# Irrigatron.net
KiCad netlist of a schematic drawn in EasyEDA
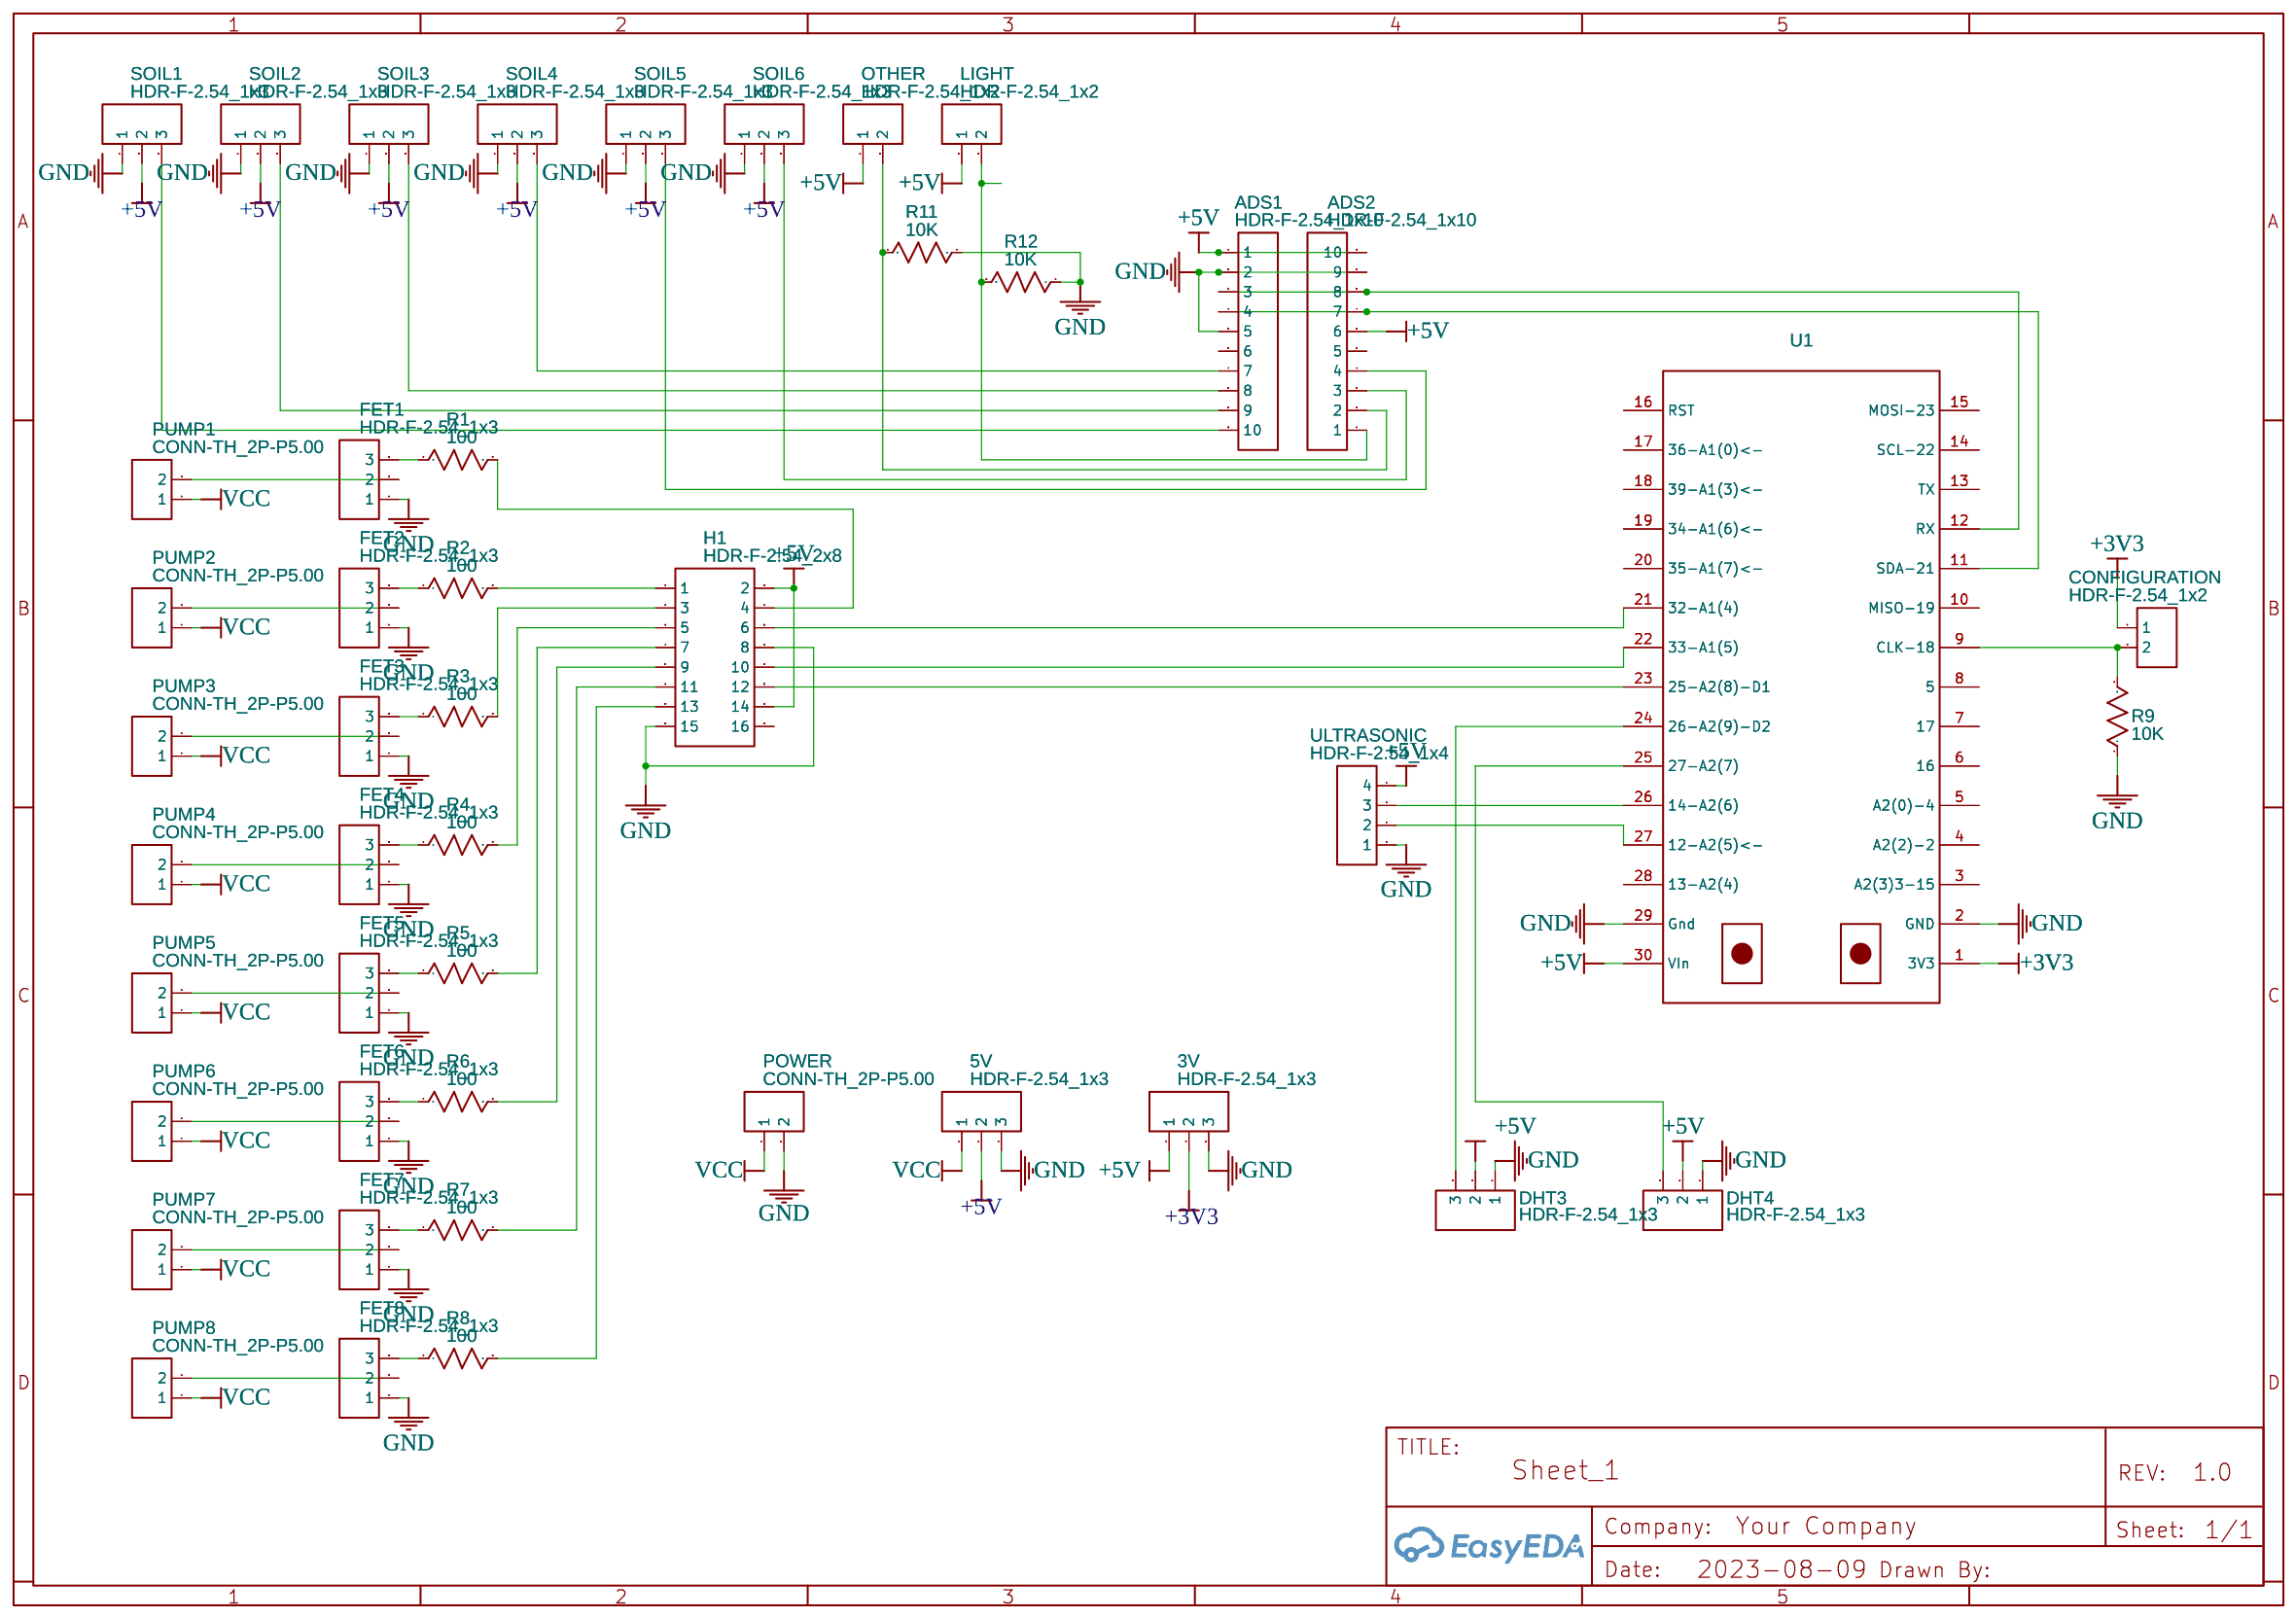
[diagram p0: schematic sheet]

(export (version "E")
  (design (tool "Eeschema 10.0.6"))
  (components
    (comp (ref "3V") (value "HDR-F-2.54_1x3") (libsource (lib "") (part "HDR-F-2.54_1x3_3")))
    (comp (ref "5V") (value "HDR-F-2.54_1x3") (libsource (lib "") (part "HDR-F-2.54_1x3")))
    (comp (ref "ADS1") (value "HDR-F-2.54_1x10") (libsource (lib "") (part "HDR-F-2.54_1x10_1")))
    (comp (ref "ADS2") (value "HDR-F-2.54_1x10") (libsource (lib "") (part "HDR-F-2.54_1x10")))
    (comp (ref "CONFIGURATION") (value "HDR-F-2.54_1x2") (libsource (lib "") (part "HDR-F-2.54_1x2_1")))
    (comp (ref "DHT3") (value "HDR-F-2.54_1x3") (libsource (lib "") (part "HDR-F-2.54_1x3_4")))
    (comp (ref "DHT4") (value "HDR-F-2.54_1x3") (libsource (lib "") (part "HDR-F-2.54_1x3_4")))
    (comp (ref "FET1") (value "HDR-F-2.54_1x3") (libsource (lib "") (part "HDR-F-2.54_1x3_1")))
    (comp (ref "FET2") (value "HDR-F-2.54_1x3") (libsource (lib "") (part "HDR-F-2.54_1x3_1")))
    (comp (ref "FET3") (value "HDR-F-2.54_1x3") (libsource (lib "") (part "HDR-F-2.54_1x3_1")))
    (comp (ref "FET4") (value "HDR-F-2.54_1x3") (libsource (lib "") (part "HDR-F-2.54_1x3_1")))
    (comp (ref "FET5") (value "HDR-F-2.54_1x3") (libsource (lib "") (part "HDR-F-2.54_1x3_1")))
    (comp (ref "FET6") (value "HDR-F-2.54_1x3") (libsource (lib "") (part "HDR-F-2.54_1x3_1")))
    (comp (ref "FET7") (value "HDR-F-2.54_1x3") (libsource (lib "") (part "HDR-F-2.54_1x3_1")))
    (comp (ref "FET8") (value "HDR-F-2.54_1x3") (libsource (lib "") (part "HDR-F-2.54_1x3_1")))
    (comp (ref "H1") (value "HDR-F-2.54_2x8") (libsource (lib "") (part "HDR-F-2.54_2x8")))
    (comp (ref "LIGHT") (value "HDR-F-2.54_1x2") (libsource (lib "") (part "HDR-F-2.54_1x2_2")))
    (comp (ref "OTHER") (value "HDR-F-2.54_1x2") (libsource (lib "") (part "HDR-F-2.54_1x2")))
    (comp (ref "POWER") (value "CONN-TH_2P-P5.00") (libsource (lib "") (part "CONN-TH_2P-P5.00_1")))
    (comp (ref "PUMP1") (value "CONN-TH_2P-P5.00") (libsource (lib "") (part "CONN-TH_2P-P5.00")))
    (comp (ref "PUMP2") (value "CONN-TH_2P-P5.00") (libsource (lib "") (part "CONN-TH_2P-P5.00")))
    (comp (ref "PUMP3") (value "CONN-TH_2P-P5.00") (libsource (lib "") (part "CONN-TH_2P-P5.00")))
    (comp (ref "PUMP4") (value "CONN-TH_2P-P5.00") (libsource (lib "") (part "CONN-TH_2P-P5.00")))
    (comp (ref "PUMP5") (value "CONN-TH_2P-P5.00") (libsource (lib "") (part "CONN-TH_2P-P5.00")))
    (comp (ref "PUMP6") (value "CONN-TH_2P-P5.00") (libsource (lib "") (part "CONN-TH_2P-P5.00")))
    (comp (ref "PUMP7") (value "CONN-TH_2P-P5.00") (libsource (lib "") (part "CONN-TH_2P-P5.00")))
    (comp (ref "PUMP8") (value "CONN-TH_2P-P5.00") (libsource (lib "") (part "CONN-TH_2P-P5.00")))
    (comp (ref "R1") (value "100") (libsource (lib "") (part "R_0603_US_1")))
    (comp (ref "R2") (value "100") (libsource (lib "") (part "R_0603_US_1")))
    (comp (ref "R3") (value "100") (libsource (lib "") (part "R_0603_US_1")))
    (comp (ref "R4") (value "100") (libsource (lib "") (part "R_0603_US_1")))
    (comp (ref "R5") (value "100") (libsource (lib "") (part "R_0603_US_1")))
    (comp (ref "R6") (value "100") (libsource (lib "") (part "R_0603_US_1")))
    (comp (ref "R7") (value "100") (libsource (lib "") (part "R_0603_US_1")))
    (comp (ref "R8") (value "100") (libsource (lib "") (part "R_0603_US_1")))
    (comp (ref "R9") (value "10K") (libsource (lib "") (part "R_0603_US_2")))
    (comp (ref "R11") (value "10K") (libsource (lib "") (part "R_0603_US")))
    (comp (ref "R12") (value "10K") (libsource (lib "") (part "R_0603_US")))
    (comp (ref "SOIL1") (value "HDR-F-2.54_1x3") (libsource (lib "") (part "HDR-F-2.54_1x3_2")))
    (comp (ref "SOIL2") (value "HDR-F-2.54_1x3") (libsource (lib "") (part "HDR-F-2.54_1x3_2")))
    (comp (ref "SOIL3") (value "HDR-F-2.54_1x3") (libsource (lib "") (part "HDR-F-2.54_1x3_2")))
    (comp (ref "SOIL4") (value "HDR-F-2.54_1x3") (libsource (lib "") (part "HDR-F-2.54_1x3_2")))
    (comp (ref "SOIL5") (value "HDR-F-2.54_1x3") (libsource (lib "") (part "HDR-F-2.54_1x3_2")))
    (comp (ref "SOIL6") (value "HDR-F-2.54_1x3") (libsource (lib "") (part "HDR-F-2.54_1x3_2")))
    (comp (ref "U1") (value "NO") (libsource (lib "") (part "DOIT ESP32 DEVKIT V1 (30pins)")))
    (comp (ref "ULTRASONIC") (value "HDR-F-2.54_1x4") (libsource (lib "") (part "HDR-F-2.54_1x4")))
  )
  (nets
    (net (code "1") (name "+3V3") (class "Default")
      (node (ref "3V") (pin "2") (pinfunction "2_2") (pintype "input"))
      (node (ref "CONFIGURATION") (pin "1") (pinfunction "1_1") (pintype "input"))
      (node (ref "U1") (pin "1") (pinfunction "3V3_1") (pintype "unspecified"))
    )
    (net (code "2") (name "+5V") (class "Default")
      (node (ref "3V") (pin "1") (pinfunction "1_1") (pintype "input"))
      (node (ref "5V") (pin "2") (pinfunction "2_2") (pintype "input"))
      (node (ref "ADS1") (pin "1") (pinfunction "1_1") (pintype "unspecified"))
      (node (ref "ADS2") (pin "10") (pinfunction "10_10") (pintype "unspecified"))
      (node (ref "ADS2") (pin "6") (pinfunction "6_6") (pintype "unspecified"))
      (node (ref "DHT3") (pin "2") (pinfunction "2_2") (pintype "input"))
      (node (ref "DHT4") (pin "2") (pinfunction "2_2") (pintype "input"))
      (node (ref "H1") (pin "14") (pinfunction "14_14") (pintype "input"))
      (node (ref "H1") (pin "2") (pinfunction "2_2") (pintype "input"))
      (node (ref "LIGHT") (pin "1") (pinfunction "1_1") (pintype "input"))
      (node (ref "OTHER") (pin "1") (pinfunction "1_1") (pintype "input"))
      (node (ref "SOIL1") (pin "2") (pinfunction "2_2") (pintype "input"))
      (node (ref "SOIL2") (pin "2") (pinfunction "2_2") (pintype "input"))
      (node (ref "SOIL3") (pin "2") (pinfunction "2_2") (pintype "input"))
      (node (ref "SOIL4") (pin "2") (pinfunction "2_2") (pintype "input"))
      (node (ref "SOIL5") (pin "2") (pinfunction "2_2") (pintype "input"))
      (node (ref "SOIL6") (pin "2") (pinfunction "2_2") (pintype "input"))
      (node (ref "U1") (pin "30") (pinfunction "VIn_30") (pintype "unspecified"))
      (node (ref "ULTRASONIC") (pin "4") (pinfunction "4_4") (pintype "unspecified"))
    )
    (net (code "3") (name "GND") (class "Default")
      (node (ref "3V") (pin "3") (pinfunction "3_3") (pintype "input"))
      (node (ref "5V") (pin "3") (pinfunction "3_3") (pintype "input"))
      (node (ref "ADS1") (pin "2") (pinfunction "2_2") (pintype "unspecified"))
      (node (ref "ADS1") (pin "5") (pinfunction "5_5") (pintype "unspecified"))
      (node (ref "ADS2") (pin "9") (pinfunction "9_9") (pintype "unspecified"))
      (node (ref "DHT3") (pin "1") (pinfunction "1_1") (pintype "input"))
      (node (ref "DHT4") (pin "1") (pinfunction "1_1") (pintype "input"))
      (node (ref "FET1") (pin "1") (pinfunction "1_1") (pintype "input"))
      (node (ref "FET2") (pin "1") (pinfunction "1_1") (pintype "input"))
      (node (ref "FET3") (pin "1") (pinfunction "1_1") (pintype "input"))
      (node (ref "FET4") (pin "1") (pinfunction "1_1") (pintype "input"))
      (node (ref "FET5") (pin "1") (pinfunction "1_1") (pintype "input"))
      (node (ref "FET6") (pin "1") (pinfunction "1_1") (pintype "input"))
      (node (ref "FET7") (pin "1") (pinfunction "1_1") (pintype "input"))
      (node (ref "FET8") (pin "1") (pinfunction "1_1") (pintype "input"))
      (node (ref "H1") (pin "15") (pinfunction "15_15") (pintype "input"))
      (node (ref "H1") (pin "8") (pinfunction "8_8") (pintype "input"))
      (node (ref "POWER") (pin "2") (pinfunction "2_2") (pintype "unspecified"))
      (node (ref "R11") (pin "1") (pinfunction "1_1") (pintype "unspecified"))
      (node (ref "R12") (pin "1") (pinfunction "1_1") (pintype "unspecified"))
      (node (ref "R9") (pin "1") (pinfunction "1_1") (pintype "unspecified"))
      (node (ref "SOIL1") (pin "1") (pinfunction "1_1") (pintype "input"))
      (node (ref "SOIL2") (pin "1") (pinfunction "1_1") (pintype "input"))
      (node (ref "SOIL3") (pin "1") (pinfunction "1_1") (pintype "input"))
      (node (ref "SOIL4") (pin "1") (pinfunction "1_1") (pintype "input"))
      (node (ref "SOIL5") (pin "1") (pinfunction "1_1") (pintype "input"))
      (node (ref "SOIL6") (pin "1") (pinfunction "1_1") (pintype "input"))
      (node (ref "U1") (pin "2") (pinfunction "GND_2") (pintype "unspecified"))
      (node (ref "U1") (pin "29") (pinfunction "Gnd_29") (pintype "unspecified"))
      (node (ref "ULTRASONIC") (pin "1") (pinfunction "1_1") (pintype "unspecified"))
    )
    (net (code "4") (name "Net-(ADS1-Pad7)") (class "Default")
      (node (ref "ADS1") (pin "7") (pinfunction "7_7") (pintype "unspecified"))
      (node (ref "SOIL4") (pin "3") (pinfunction "3_3") (pintype "input"))
    )
    (net (code "5") (name "Net-(ADS1-Pad8)") (class "Default")
      (node (ref "ADS1") (pin "8") (pinfunction "8_8") (pintype "unspecified"))
      (node (ref "SOIL3") (pin "3") (pinfunction "3_3") (pintype "input"))
    )
    (net (code "6") (name "Net-(ADS1-Pad9)") (class "Default")
      (node (ref "ADS1") (pin "9") (pinfunction "9_9") (pintype "unspecified"))
      (node (ref "SOIL2") (pin "3") (pinfunction "3_3") (pintype "input"))
    )
    (net (code "7") (name "Net-(ADS1-Pad10)") (class "Default")
      (node (ref "ADS1") (pin "10") (pinfunction "10_10") (pintype "unspecified"))
      (node (ref "SOIL1") (pin "3") (pinfunction "3_3") (pintype "input"))
    )
    (net (code "8") (name "Net-(ADS2-Pad1)") (class "Default")
      (node (ref "ADS2") (pin "1") (pinfunction "1_1") (pintype "unspecified"))
      (node (ref "LIGHT") (pin "2") (pinfunction "2_2") (pintype "input"))
      (node (ref "R12") (pin "2") (pinfunction "2_2") (pintype "unspecified"))
    )
    (net (code "9") (name "Net-(ADS2-Pad2)") (class "Default")
      (node (ref "ADS2") (pin "2") (pinfunction "2_2") (pintype "unspecified"))
      (node (ref "OTHER") (pin "2") (pinfunction "2_2") (pintype "input"))
      (node (ref "R11") (pin "2") (pinfunction "2_2") (pintype "unspecified"))
    )
    (net (code "10") (name "Net-(ADS2-Pad3)") (class "Default")
      (node (ref "ADS2") (pin "3") (pinfunction "3_3") (pintype "unspecified"))
      (node (ref "SOIL6") (pin "3") (pinfunction "3_3") (pintype "input"))
    )
    (net (code "11") (name "Net-(ADS2-Pad4)") (class "Default")
      (node (ref "ADS2") (pin "4") (pinfunction "4_4") (pintype "unspecified"))
      (node (ref "SOIL5") (pin "3") (pinfunction "3_3") (pintype "input"))
    )
    (net (code "12") (name "Net-(FET1-Pad2)") (class "Default")
      (node (ref "FET1") (pin "2") (pinfunction "2_2") (pintype "input"))
      (node (ref "PUMP1") (pin "2") (pinfunction "2_2") (pintype "unspecified"))
    )
    (net (code "13") (name "Net-(FET1-Pad3)") (class "Default")
      (node (ref "FET1") (pin "3") (pinfunction "3_3") (pintype "input"))
      (node (ref "R1") (pin "1") (pinfunction "1_1") (pintype "unspecified"))
    )
    (net (code "14") (name "Net-(FET2-Pad2)") (class "Default")
      (node (ref "FET2") (pin "2") (pinfunction "2_2") (pintype "input"))
      (node (ref "PUMP2") (pin "2") (pinfunction "2_2") (pintype "unspecified"))
    )
    (net (code "15") (name "Net-(FET2-Pad3)") (class "Default")
      (node (ref "FET2") (pin "3") (pinfunction "3_3") (pintype "input"))
      (node (ref "R2") (pin "1") (pinfunction "1_1") (pintype "unspecified"))
    )
    (net (code "16") (name "Net-(FET3-Pad3)") (class "Default")
      (node (ref "FET3") (pin "3") (pinfunction "3_3") (pintype "input"))
      (node (ref "R3") (pin "1") (pinfunction "1_1") (pintype "unspecified"))
    )
    (net (code "17") (name "Net-(FET4-Pad2)") (class "Default")
      (node (ref "FET4") (pin "2") (pinfunction "2_2") (pintype "input"))
      (node (ref "PUMP4") (pin "2") (pinfunction "2_2") (pintype "unspecified"))
    )
    (net (code "18") (name "Net-(FET4-Pad3)") (class "Default")
      (node (ref "FET4") (pin "3") (pinfunction "3_3") (pintype "input"))
      (node (ref "R4") (pin "1") (pinfunction "1_1") (pintype "unspecified"))
    )
    (net (code "19") (name "Net-(FET5-Pad2)") (class "Default")
      (node (ref "FET5") (pin "2") (pinfunction "2_2") (pintype "input"))
      (node (ref "PUMP5") (pin "2") (pinfunction "2_2") (pintype "unspecified"))
    )
    (net (code "20") (name "Net-(FET5-Pad3)") (class "Default")
      (node (ref "FET5") (pin "3") (pinfunction "3_3") (pintype "input"))
      (node (ref "R5") (pin "1") (pinfunction "1_1") (pintype "unspecified"))
    )
    (net (code "21") (name "Net-(FET6-Pad2)") (class "Default")
      (node (ref "FET6") (pin "2") (pinfunction "2_2") (pintype "input"))
      (node (ref "PUMP6") (pin "2") (pinfunction "2_2") (pintype "unspecified"))
    )
    (net (code "22") (name "Net-(FET6-Pad3)") (class "Default")
      (node (ref "FET6") (pin "3") (pinfunction "3_3") (pintype "input"))
      (node (ref "R6") (pin "1") (pinfunction "1_1") (pintype "unspecified"))
    )
    (net (code "23") (name "Net-(FET7-Pad2)") (class "Default")
      (node (ref "FET7") (pin "2") (pinfunction "2_2") (pintype "input"))
      (node (ref "PUMP7") (pin "2") (pinfunction "2_2") (pintype "unspecified"))
    )
    (net (code "24") (name "Net-(FET7-Pad3)") (class "Default")
      (node (ref "FET7") (pin "3") (pinfunction "3_3") (pintype "input"))
      (node (ref "R7") (pin "1") (pinfunction "1_1") (pintype "unspecified"))
    )
    (net (code "25") (name "Net-(FET8-Pad2)") (class "Default")
      (node (ref "FET8") (pin "2") (pinfunction "2_2") (pintype "input"))
      (node (ref "PUMP8") (pin "2") (pinfunction "2_2") (pintype "unspecified"))
    )
    (net (code "26") (name "Net-(FET8-Pad3)") (class "Default")
      (node (ref "FET8") (pin "3") (pinfunction "3_3") (pintype "input"))
      (node (ref "R8") (pin "1") (pinfunction "1_1") (pintype "unspecified"))
    )
    (net (code "27") (name "Net-(H1-Pad1)") (class "Default")
      (node (ref "H1") (pin "1") (pinfunction "1_1") (pintype "input"))
      (node (ref "R2") (pin "2") (pinfunction "2_2") (pintype "unspecified"))
    )
    (net (code "28") (name "Net-(H1-Pad3)") (class "Default")
      (node (ref "H1") (pin "3") (pinfunction "3_3") (pintype "input"))
      (node (ref "R3") (pin "2") (pinfunction "2_2") (pintype "unspecified"))
    )
    (net (code "29") (name "Net-(H1-Pad4)") (class "Default")
      (node (ref "H1") (pin "4") (pinfunction "4_4") (pintype "input"))
      (node (ref "R1") (pin "2") (pinfunction "2_2") (pintype "unspecified"))
    )
    (net (code "30") (name "Net-(H1-Pad5)") (class "Default")
      (node (ref "H1") (pin "5") (pinfunction "5_5") (pintype "input"))
      (node (ref "R4") (pin "2") (pinfunction "2_2") (pintype "unspecified"))
    )
    (net (code "31") (name "Net-(H1-Pad7)") (class "Default")
      (node (ref "H1") (pin "7") (pinfunction "7_7") (pintype "input"))
      (node (ref "R5") (pin "2") (pinfunction "2_2") (pintype "unspecified"))
    )
    (net (code "32") (name "Net-(H1-Pad9)") (class "Default")
      (node (ref "H1") (pin "9") (pinfunction "9_9") (pintype "input"))
      (node (ref "R6") (pin "2") (pinfunction "2_2") (pintype "unspecified"))
    )
    (net (code "33") (name "Net-(H1-Pad11)") (class "Default")
      (node (ref "H1") (pin "11") (pinfunction "11_11") (pintype "input"))
      (node (ref "R7") (pin "2") (pinfunction "2_2") (pintype "unspecified"))
    )
    (net (code "34") (name "Net-(H1-Pad13)") (class "Default")
      (node (ref "H1") (pin "13") (pinfunction "13_13") (pintype "input"))
      (node (ref "R8") (pin "2") (pinfunction "2_2") (pintype "unspecified"))
    )
    (net (code "35") (name "Net-(U1-12-A2(5)<-)") (class "Default")
      (node (ref "U1") (pin "27") (pinfunction "12-A2(5)<-_27") (pintype "unspecified"))
      (node (ref "ULTRASONIC") (pin "2") (pinfunction "2_2") (pintype "unspecified"))
    )
    (net (code "36") (name "Net-(U1-14-A2(6))") (class "Default")
      (node (ref "U1") (pin "26") (pinfunction "14-A2(6)_26") (pintype "unspecified"))
      (node (ref "ULTRASONIC") (pin "3") (pinfunction "3_3") (pintype "unspecified"))
    )
    (net (code "37") (name "Net-(U1-25-A2(8)-D1)") (class "Default")
      (node (ref "H1") (pin "12") (pinfunction "12_12") (pintype "input"))
      (node (ref "U1") (pin "23") (pinfunction "25-A2(8)-D1_23") (pintype "unspecified"))
    )
    (net (code "38") (name "Net-(U1-26-A2(9)-D2)") (class "Default")
      (node (ref "DHT3") (pin "3") (pinfunction "3_3") (pintype "input"))
      (node (ref "U1") (pin "24") (pinfunction "26-A2(9)-D2_24") (pintype "unspecified"))
    )
    (net (code "39") (name "Net-(U1-27-A2(7))") (class "Default")
      (node (ref "DHT4") (pin "3") (pinfunction "3_3") (pintype "input"))
      (node (ref "U1") (pin "25") (pinfunction "27-A2(7)_25") (pintype "unspecified"))
    )
    (net (code "40") (name "Net-(U1-32-A1(4))") (class "Default")
      (node (ref "H1") (pin "6") (pinfunction "6_6") (pintype "input"))
      (node (ref "U1") (pin "21") (pinfunction "32-A1(4)_21") (pintype "unspecified"))
    )
    (net (code "41") (name "Net-(U1-33-A1(5))") (class "Default")
      (node (ref "H1") (pin "10") (pinfunction "10_10") (pintype "input"))
      (node (ref "U1") (pin "22") (pinfunction "33-A1(5)_22") (pintype "unspecified"))
    )
    (net (code "42") (name "Net-(U1-CLK-18)") (class "Default")
      (node (ref "CONFIGURATION") (pin "2") (pinfunction "2_2") (pintype "input"))
      (node (ref "R9") (pin "2") (pinfunction "2_2") (pintype "unspecified"))
      (node (ref "U1") (pin "9") (pinfunction "CLK-18_9") (pintype "unspecified"))
    )
    (net (code "43") (name "Net-(U1-RX)") (class "Default")
      (node (ref "ADS1") (pin "3") (pinfunction "3_3") (pintype "unspecified"))
      (node (ref "ADS2") (pin "8") (pinfunction "8_8") (pintype "unspecified"))
      (node (ref "U1") (pin "12") (pinfunction "RX_12") (pintype "unspecified"))
    )
    (net (code "44") (name "Net-(U1-SDA-21)") (class "Default")
      (node (ref "ADS1") (pin "4") (pinfunction "4_4") (pintype "unspecified"))
      (node (ref "ADS2") (pin "7") (pinfunction "7_7") (pintype "unspecified"))
      (node (ref "U1") (pin "11") (pinfunction "SDA-21_11") (pintype "unspecified"))
    )
    (net (code "45") (name "VCC") (class "Default")
      (node (ref "5V") (pin "1") (pinfunction "1_1") (pintype "input"))
      (node (ref "POWER") (pin "1") (pinfunction "1_1") (pintype "unspecified"))
      (node (ref "PUMP1") (pin "1") (pinfunction "1_1") (pintype "unspecified"))
      (node (ref "PUMP2") (pin "1") (pinfunction "1_1") (pintype "unspecified"))
      (node (ref "PUMP3") (pin "1") (pinfunction "1_1") (pintype "unspecified"))
      (node (ref "PUMP4") (pin "1") (pinfunction "1_1") (pintype "unspecified"))
      (node (ref "PUMP5") (pin "1") (pinfunction "1_1") (pintype "unspecified"))
      (node (ref "PUMP6") (pin "1") (pinfunction "1_1") (pintype "unspecified"))
      (node (ref "PUMP7") (pin "1") (pinfunction "1_1") (pintype "unspecified"))
      (node (ref "PUMP8") (pin "1") (pinfunction "1_1") (pintype "unspecified"))
    )
    (net (code "46") (name "unconnected-(ADS1-Pad6)") (class "Default")
      (node (ref "ADS1") (pin "6") (pinfunction "6_6") (pintype "unspecified"))
    )
    (net (code "47") (name "unconnected-(ADS2-Pad5)") (class "Default")
      (node (ref "ADS2") (pin "5") (pinfunction "5_5") (pintype "unspecified"))
    )
    (net (code "48") (name "unconnected-(FET3-Pad2)") (class "Default")
      (node (ref "FET3") (pin "2") (pinfunction "2_2") (pintype "input"))
    )
    (net (code "49") (name "unconnected-(H1-Pad16)") (class "Default")
      (node (ref "H1") (pin "16") (pinfunction "16_16") (pintype "input"))
    )
    (net (code "50") (name "unconnected-(PUMP3-Pad2)") (class "Default")
      (node (ref "PUMP3") (pin "2") (pinfunction "2_2") (pintype "unspecified"))
    )
    (net (code "51") (name "unconnected-(U1-5-Pad8)") (class "Default")
      (node (ref "U1") (pin "8") (pinfunction "5_8") (pintype "unspecified"))
    )
    (net (code "52") (name "unconnected-(U1-13-A2(4)-Pad28)") (class "Default")
      (node (ref "U1") (pin "28") (pinfunction "13-A2(4)_28") (pintype "unspecified"))
    )
    (net (code "53") (name "unconnected-(U1-16-Pad6)") (class "Default")
      (node (ref "U1") (pin "6") (pinfunction "16_6") (pintype "unspecified"))
    )
    (net (code "54") (name "unconnected-(U1-17-Pad7)") (class "Default")
      (node (ref "U1") (pin "7") (pinfunction "17_7") (pintype "unspecified"))
    )
    (net (code "55") (name "unconnected-(U1-34-A1(6)<--Pad19)") (class "Default")
      (node (ref "U1") (pin "19") (pinfunction "34-A1(6)<-_19") (pintype "unspecified"))
    )
    (net (code "56") (name "unconnected-(U1-35-A1(7)<--Pad20)") (class "Default")
      (node (ref "U1") (pin "20") (pinfunction "35-A1(7)<-_20") (pintype "unspecified"))
    )
    (net (code "57") (name "unconnected-(U1-36-A1(0)<--Pad17)") (class "Default")
      (node (ref "U1") (pin "17") (pinfunction "36-A1(0)<-_17") (pintype "unspecified"))
    )
    (net (code "58") (name "unconnected-(U1-39-A1(3)<--Pad18)") (class "Default")
      (node (ref "U1") (pin "18") (pinfunction "39-A1(3)<-_18") (pintype "unspecified"))
    )
    (net (code "59") (name "unconnected-(U1-A2(0)-4-Pad5)") (class "Default")
      (node (ref "U1") (pin "5") (pinfunction "A2(0)-4_5") (pintype "unspecified"))
    )
    (net (code "60") (name "unconnected-(U1-A2(2)-2-Pad4)") (class "Default")
      (node (ref "U1") (pin "4") (pinfunction "A2(2)-2_4") (pintype "unspecified"))
    )
    (net (code "61") (name "unconnected-(U1-A2(3)3-15-Pad3)") (class "Default")
      (node (ref "U1") (pin "3") (pinfunction "A2(3)3-15_3") (pintype "unspecified"))
    )
    (net (code "62") (name "unconnected-(U1-MISO-19-Pad10)") (class "Default")
      (node (ref "U1") (pin "10") (pinfunction "MISO-19_10") (pintype "unspecified"))
    )
    (net (code "63") (name "unconnected-(U1-MOSI-23-Pad15)") (class "Default")
      (node (ref "U1") (pin "15") (pinfunction "MOSI-23_15") (pintype "unspecified"))
    )
    (net (code "64") (name "unconnected-(U1-RST-Pad16)") (class "Default")
      (node (ref "U1") (pin "16") (pinfunction "RST_16") (pintype "unspecified"))
    )
    (net (code "65") (name "unconnected-(U1-SCL-22-Pad14)") (class "Default")
      (node (ref "U1") (pin "14") (pinfunction "SCL-22_14") (pintype "unspecified"))
    )
    (net (code "66") (name "unconnected-(U1-TX-Pad13)") (class "Default")
      (node (ref "U1") (pin "13") (pinfunction "TX_13") (pintype "unspecified"))
    )
  )
)
